# Interface.net
KiCad netlist of a schematic drawn in Altium Designer
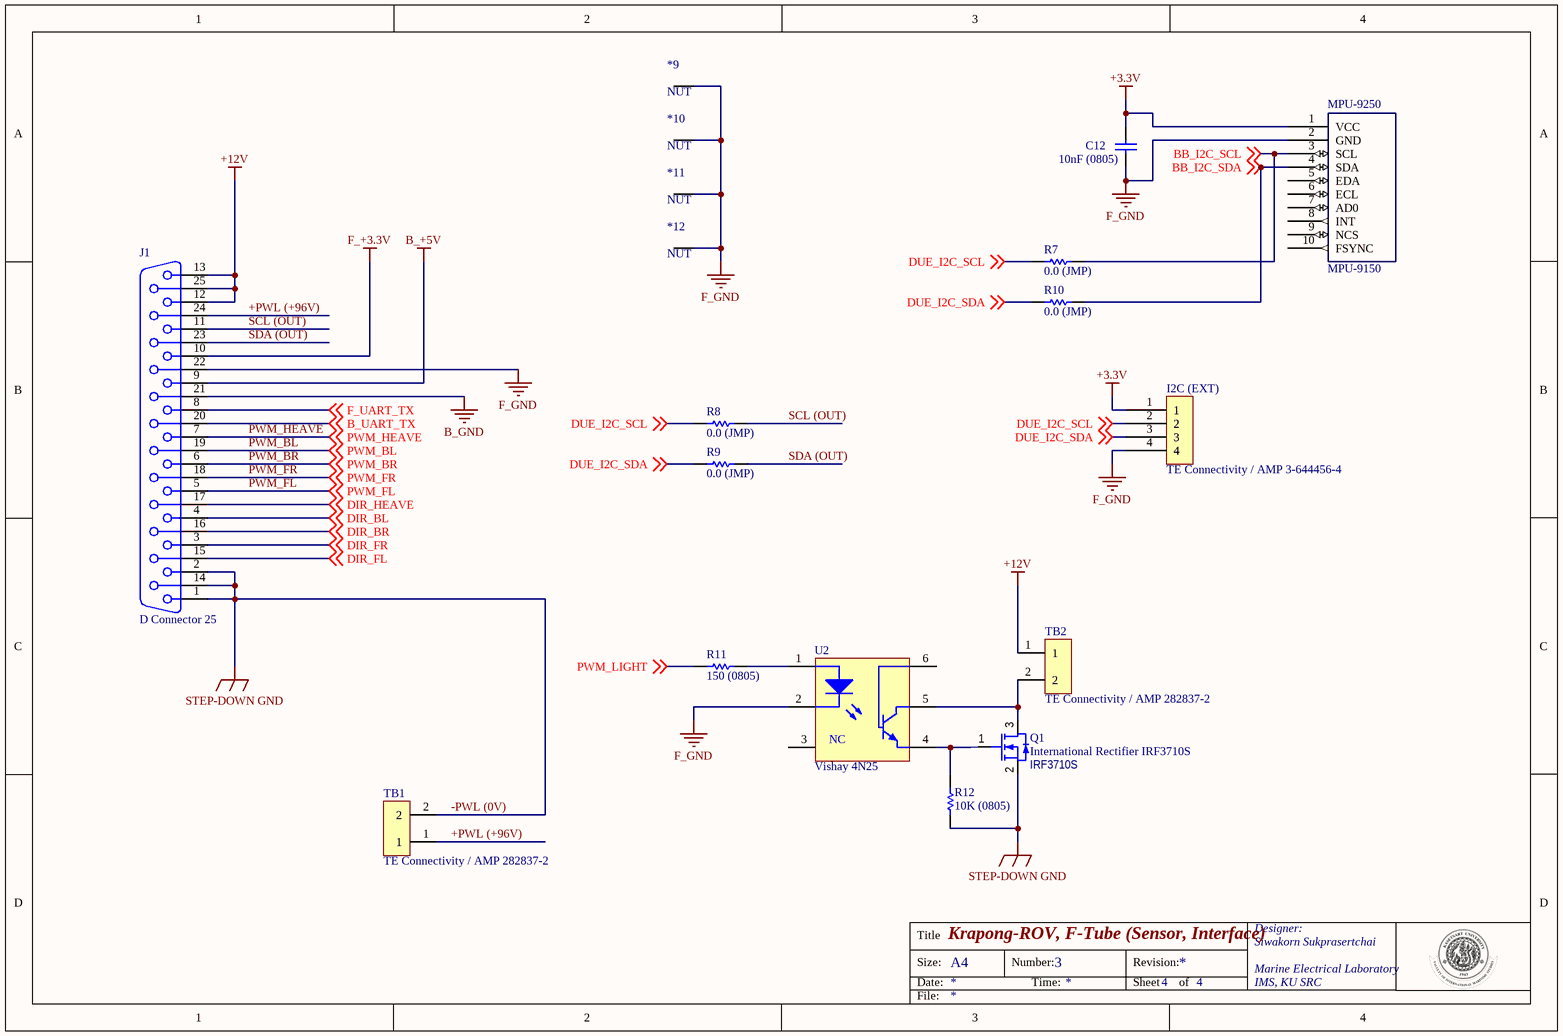
[diagram p0: Interface.SchDoc]

(export (version "E")
  (design (tool "Eeschema 10.0.6"))
  (components
    (comp (ref "*9")
      (value "NUT")
      (footprint "PCB-pcj1l6roq5gpi9u538ps-1")
      (description "Standoff; 12 mm; M3 x 0.5; Brass; Hex; Nickel Plate; 8 in.; 8 in.")
      (fields (field (name "MANUFACTURER PART NUMBER") "24314"))
      (libsource (lib "CommunityVault") (part "CMP-5ddc94dc62be821b-2"))
    )
    (comp (ref "*10")
      (value "NUT")
      (footprint "PCB-pcj1l6roq5gpi9u538ps-1")
      (description "Standoff; 12 mm; M3 x 0.5; Brass; Hex; Nickel Plate; 8 in.; 8 in.")
      (fields (field (name "MANUFACTURER PART NUMBER") "24314"))
      (libsource (lib "CommunityVault") (part "CMP-5ddc94dc62be821b-2"))
    )
    (comp (ref "*11")
      (value "NUT")
      (footprint "PCB-pcj1l6roq5gpi9u538ps-1")
      (description "Standoff; 12 mm; M3 x 0.5; Brass; Hex; Nickel Plate; 8 in.; 8 in.")
      (fields (field (name "MANUFACTURER PART NUMBER") "24314"))
      (libsource (lib "CommunityVault") (part "CMP-5ddc94dc62be821b-2"))
    )
    (comp (ref "*12")
      (value "NUT")
      (footprint "PCB-pcj1l6roq5gpi9u538ps-1")
      (description "Standoff; 12 mm; M3 x 0.5; Brass; Hex; Nickel Plate; 8 in.; 8 in.")
      (fields (field (name "MANUFACTURER PART NUMBER") "24314"))
      (libsource (lib "CommunityVault") (part "CMP-5ddc94dc62be821b-2"))
    )
    (comp (ref "C12")
      (value "10nF (0805)")
      (footprint "CAPC2013X94X50NL20T25")
      (description "CAP CER 10NF 50V 5% X7R 0805")
      (fields (field (name "MANUFACTURER PART NUMBER") "08055C103JAT2A"))
      (libsource (lib "FavoritesLibrary") (part "CAP-2"))
    )
    (comp (ref "I2C (EXT)")
      (value "TE Connectivity / AMP 3-644456-4")
      (footprint "PCB-rz6n0fnwkrymh4bzf5j3-1")
      (description "Board-To-Board Connector, MTA-100 Series, Through Hole, Header, 4, 2.54 mm, Tin Plated Contacts")
      (fields (field (name "MANUFACTURER PART NUMBER") "3-644456-4"))
      (libsource (lib "FavoritesLibrary") (part "SYM-aedf658f79ea7118-1"))
    )
    (comp (ref "J1")
      (value "D Connector 25")
      (footprint "PCB-w6wyndea0hgjvu195v0z-1")
      (description "D Sub Connector, Amplimite HD-20, Amplimite HD-20 Series, DB, Plug, 25, Metal, Solder")
      (fields (field (name "MANUFACTURER PART NUMBER") "5747842-4"))
      (libsource (lib "CommunityVault") (part "CMP-d8a713f745850760-3"))
    )
    (comp (ref "MPU-9250")
      (value "MPU-9150")
      (footprint "PCB-qjnj89ydof8zhvyyt2pp-1")
      (description "MPU-9150 or GY-Series")
      (libsource (lib "FavoritesLibrary") (part "SYM-arxnhq8o6hyvnzrq5u03-1"))
    )
    (comp (ref "Q1")
      (value "International Rectifier IRF3710S")
      (footprint "PCB-knfcvcmaqkz1jt91xuml-1")
      (description "100V Single N-Channel HEXFET Power MOSFET in a D2-Pak package")
      (fields (field (name "VLAUE") "IRF3710S") (field (name "MANUFACTURER PART NUMBER") "IRF3710S"))
      (libsource (lib "CommunityVault") (part "CMP-3cf2f5f9d0cee335-1"))
    )
    (comp (ref "R7")
      (value "0.0 (JMP)")
      (footprint "RESC2013X60X35ML10T20")
      (description "Res Thick Film 0805 0 Ohm Molded SMD Paper T/R")
      (fields (field (name "MANUFACTURER PART NUMBER") "RC0805FR-070RL"))
      (libsource (lib "FavoritesLibrary") (part "SYM-f3d13a5618eb2c16-1"))
    )
    (comp (ref "R8")
      (value "0.0 (JMP)")
      (footprint "RESC2013X60X35ML10T20")
      (description "Res Thick Film 0805 0 Ohm Molded SMD Paper T/R")
      (fields (field (name "MANUFACTURER PART NUMBER") "RC0805FR-070RL"))
      (libsource (lib "FavoritesLibrary") (part "SYM-f3d13a5618eb2c16-1"))
    )
    (comp (ref "R9")
      (value "0.0 (JMP)")
      (footprint "RESC2013X60X35ML10T20")
      (description "Res Thick Film 0805 0 Ohm Molded SMD Paper T/R")
      (fields (field (name "MANUFACTURER PART NUMBER") "RC0805FR-070RL"))
      (libsource (lib "FavoritesLibrary") (part "SYM-f3d13a5618eb2c16-1"))
    )
    (comp (ref "R10")
      (value "0.0 (JMP)")
      (footprint "RESC2013X60X35ML10T20")
      (description "Res Thick Film 0805 0 Ohm Molded SMD Paper T/R")
      (fields (field (name "MANUFACTURER PART NUMBER") "RC0805FR-070RL"))
      (libsource (lib "FavoritesLibrary") (part "SYM-f3d13a5618eb2c16-1"))
    )
    (comp (ref "R11")
      (value "150 (0805)")
      (footprint "RESC2013X60X40NL15T20")
      (description "RES SMD 10K OHM 1% 1/3W 0805")
      (libsource (lib "FavoritesLibrary") (part "RES-2"))
    )
    (comp (ref "R12")
      (value "10K (0805)")
      (footprint "RESC2013X60X40NL15T20")
      (description "RES SMD 10K OHM 1% 1/3W 0805")
      (libsource (lib "FavoritesLibrary") (part "RES-2"))
    )
    (comp (ref "TB1")
      (value "TE Connectivity / AMP 282837-2")
      (footprint "PCB-suk0edwv8aq1tcw7107x-1")
      (description "Connector Terminal Blocks Receptacle 2 Position 5.08mm Solder Straight Thru-Hole 13.5A/Contact")
      (fields (field (name "MANUFACTURER PART NUMBER") "282837-2"))
      (libsource (lib "") (part "CMP-50ff9bac89d88f38-13_1"))
    )
    (comp (ref "TB2")
      (value "TE Connectivity / AMP 282837-2")
      (footprint "PCB-suk0edwv8aq1tcw7107x-1")
      (description "Connector Terminal Blocks Receptacle 2 Position 5.08mm Solder Straight Thru-Hole 13.5A/Contact")
      (fields (field (name "MANUFACTURER PART NUMBER") "282837-2"))
      (libsource (lib "CommunityVault") (part "CMP-50ff9bac89d88f38-13"))
    )
    (comp (ref "U2")
      (value "Vishay 4N25")
      (footprint "PCB-jnahbn6qvly565f94r9b-1")
      (description "1 Channel Transistor Output Optocoupler 1 Channel Transistor Output Optocoupler")
      (fields (field (name "MANUFACTURER PART NUMBER") "4N25"))
      (libsource (lib "FavoritesLibrary") (part "SYM-1bb3d1f4e47dc474-1"))
    )
  )
  (nets
    (net (code "1") (name "+3.3V") (class "Default")
      (node (ref "C12") (pin "2") (pinfunction "2_2") (pintype "passive"))
      (node (ref "I2C (EXT)") (pin "1") (pinfunction "1_1") (pintype "passive"))
      (node (ref "MPU-9250") (pin "1") (pinfunction "VCC_1") (pintype "power_in"))
    )
    (net (code "2") (name "+12V") (class "Default")
      (node (ref "J1") (pin "12") (pinfunction "12_12") (pintype "passive"))
      (node (ref "J1") (pin "13") (pinfunction "13_13") (pintype "passive"))
      (node (ref "J1") (pin "25") (pinfunction "25_25") (pintype "passive"))
      (node (ref "TB2") (pin "1") (pinfunction "1_1") (pintype "passive"))
    )
    (net (code "3") (name "/+PWL (+96V)") (class "Default")
      (node (ref "J1") (pin "24") (pinfunction "24_24") (pintype "passive"))
      (node (ref "TB1") (pin "1") (pinfunction "1_1") (pintype "passive"))
    )
    (net (code "4") (name "/SCL (OUT)") (class "Default")
      (node (ref "J1") (pin "11") (pinfunction "11_11") (pintype "passive"))
      (node (ref "R8") (pin "1") (pinfunction "1_1") (pintype "passive"))
    )
    (net (code "5") (name "/SDA (OUT)") (class "Default")
      (node (ref "J1") (pin "23") (pinfunction "23_23") (pintype "passive"))
      (node (ref "R9") (pin "1") (pinfunction "1_1") (pintype "passive"))
    )
    (net (code "6") (name "BB_I2C_SCL") (class "Default")
      (node (ref "MPU-9250") (pin "3") (pinfunction "SCL_3") (pintype "bidirectional"))
      (node (ref "R7") (pin "1") (pinfunction "1_1") (pintype "passive"))
    )
    (net (code "7") (name "BB_I2C_SDA") (class "Default")
      (node (ref "MPU-9250") (pin "4") (pinfunction "SDA_4") (pintype "bidirectional"))
      (node (ref "R10") (pin "1") (pinfunction "1_1") (pintype "passive"))
    )
    (net (code "8") (name "B_+5V") (class "Default")
      (node (ref "J1") (pin "9") (pinfunction "9_9") (pintype "passive"))
    )
    (net (code "9") (name "B_GND") (class "Default")
      (node (ref "J1") (pin "21") (pinfunction "21_21") (pintype "passive"))
    )
    (net (code "10") (name "B_UART_TX") (class "Default")
      (node (ref "J1") (pin "20") (pinfunction "20_20") (pintype "passive"))
    )
    (net (code "11") (name "DIR_BL") (class "Default")
      (node (ref "J1") (pin "4") (pinfunction "4_4") (pintype "passive"))
    )
    (net (code "12") (name "DIR_BR") (class "Default")
      (node (ref "J1") (pin "16") (pinfunction "16_16") (pintype "passive"))
    )
    (net (code "13") (name "DIR_FL") (class "Default")
      (node (ref "J1") (pin "15") (pinfunction "15_15") (pintype "passive"))
    )
    (net (code "14") (name "DIR_FR") (class "Default")
      (node (ref "J1") (pin "3") (pinfunction "3_3") (pintype "passive"))
    )
    (net (code "15") (name "DIR_HEAVE") (class "Default")
      (node (ref "J1") (pin "17") (pinfunction "17_17") (pintype "passive"))
    )
    (net (code "16") (name "DUE_I2C_SCL") (class "Default")
      (node (ref "I2C (EXT)") (pin "2") (pinfunction "2_2") (pintype "passive"))
      (node (ref "R7") (pin "2") (pinfunction "2_2") (pintype "passive"))
      (node (ref "R8") (pin "2") (pinfunction "2_2") (pintype "passive"))
    )
    (net (code "17") (name "DUE_I2C_SDA") (class "Default")
      (node (ref "I2C (EXT)") (pin "3") (pinfunction "3_3") (pintype "passive"))
      (node (ref "R10") (pin "2") (pinfunction "2_2") (pintype "passive"))
      (node (ref "R9") (pin "2") (pinfunction "2_2") (pintype "passive"))
    )
    (net (code "18") (name "F_+3.3V") (class "Default")
      (node (ref "J1") (pin "10") (pinfunction "10_10") (pintype "passive"))
    )
    (net (code "19") (name "F_GND") (class "Default")
      (node (ref "*10") (pin "0") (pinfunction "0_0") (pintype "power_in"))
      (node (ref "*11") (pin "0") (pinfunction "0_0") (pintype "power_in"))
      (node (ref "*12") (pin "0") (pinfunction "0_0") (pintype "power_in"))
      (node (ref "*9") (pin "0") (pinfunction "0_0") (pintype "power_in"))
      (node (ref "C12") (pin "1") (pinfunction "1_1") (pintype "passive"))
      (node (ref "I2C (EXT)") (pin "4") (pinfunction "4_4") (pintype "passive"))
      (node (ref "J1") (pin "22") (pinfunction "22_22") (pintype "passive"))
      (node (ref "MPU-9250") (pin "2") (pinfunction "GND_2") (pintype "power_in"))
      (node (ref "U2") (pin "2") (pinfunction "2_2") (pintype "passive"))
    )
    (net (code "20") (name "F_UART_TX") (class "Default")
      (node (ref "J1") (pin "8") (pinfunction "8_8") (pintype "passive"))
    )
    (net (code "21") (name "Net-(Q1-D)") (class "Default")
      (node (ref "Q1") (pin "3") (pinfunction "D_3") (pintype "passive"))
      (node (ref "TB2") (pin "2") (pinfunction "2_2") (pintype "passive"))
      (node (ref "U2") (pin "5") (pinfunction "5_5") (pintype "passive"))
    )
    (net (code "22") (name "Net-(Q1-G)") (class "Default")
      (node (ref "Q1") (pin "1") (pinfunction "G_1") (pintype "passive"))
      (node (ref "R12") (pin "2") (pinfunction "2_2") (pintype "passive"))
      (node (ref "U2") (pin "4") (pinfunction "4_4") (pintype "passive"))
    )
    (net (code "23") (name "Net-(R11-Pad1)") (class "Default")
      (node (ref "R11") (pin "1") (pinfunction "1_1") (pintype "passive"))
      (node (ref "U2") (pin "1") (pinfunction "1_1") (pintype "passive"))
    )
    (net (code "24") (name "PWM_BL") (class "Default")
      (node (ref "J1") (pin "19") (pinfunction "19_19") (pintype "passive"))
    )
    (net (code "25") (name "PWM_BR") (class "Default")
      (node (ref "J1") (pin "6") (pinfunction "6_6") (pintype "passive"))
    )
    (net (code "26") (name "PWM_FL") (class "Default")
      (node (ref "J1") (pin "5") (pinfunction "5_5") (pintype "passive"))
    )
    (net (code "27") (name "PWM_FR") (class "Default")
      (node (ref "J1") (pin "18") (pinfunction "18_18") (pintype "passive"))
    )
    (net (code "28") (name "PWM_HEAVE") (class "Default")
      (node (ref "J1") (pin "7") (pinfunction "7_7") (pintype "passive"))
    )
    (net (code "29") (name "PWM_LIGHT") (class "Default")
      (node (ref "R11") (pin "2") (pinfunction "2_2") (pintype "passive"))
    )
    (net (code "30") (name "STEP-DOWN GND") (class "Default")
      (node (ref "J1") (pin "1") (pinfunction "1_1") (pintype "passive"))
      (node (ref "J1") (pin "14") (pinfunction "14_14") (pintype "passive"))
      (node (ref "J1") (pin "2") (pinfunction "2_2") (pintype "passive"))
      (node (ref "Q1") (pin "2") (pinfunction "S_2") (pintype "passive"))
      (node (ref "R12") (pin "1") (pinfunction "1_1") (pintype "passive"))
      (node (ref "TB1") (pin "2") (pinfunction "2_2") (pintype "passive"))
    )
    (net (code "31") (name "unconnected-(MPU-9250-AD0-Pad7)") (class "Default")
      (node (ref "MPU-9250") (pin "7") (pinfunction "AD0_7") (pintype "bidirectional"))
    )
    (net (code "32") (name "unconnected-(MPU-9250-ECL-Pad6)") (class "Default")
      (node (ref "MPU-9250") (pin "6") (pinfunction "ECL_6") (pintype "bidirectional"))
    )
    (net (code "33") (name "unconnected-(MPU-9250-EDA-Pad5)") (class "Default")
      (node (ref "MPU-9250") (pin "5") (pinfunction "EDA_5") (pintype "bidirectional"))
    )
    (net (code "34") (name "unconnected-(MPU-9250-FSYNC-Pad10)") (class "Default")
      (node (ref "MPU-9250") (pin "10") (pinfunction "FSYNC_10") (pintype "output"))
    )
    (net (code "35") (name "unconnected-(MPU-9250-INT-Pad8)") (class "Default")
      (node (ref "MPU-9250") (pin "8") (pinfunction "INT_8") (pintype "output"))
    )
    (net (code "36") (name "unconnected-(MPU-9250-NCS-Pad9)") (class "Default")
      (node (ref "MPU-9250") (pin "9") (pinfunction "NCS_9") (pintype "bidirectional"))
    )
    (net (code "37") (name "unconnected-(U2-Pad3)") (class "Default")
      (node (ref "U2") (pin "3") (pinfunction "3_3") (pintype "passive"))
    )
    (net (code "38") (name "unconnected-(U2-Pad6)") (class "Default")
      (node (ref "U2") (pin "6") (pinfunction "6_6") (pintype "passive"))
    )
  )
)
